# BikeLight_POC.net
KiCad netlist of a schematic drawn in EAGLE
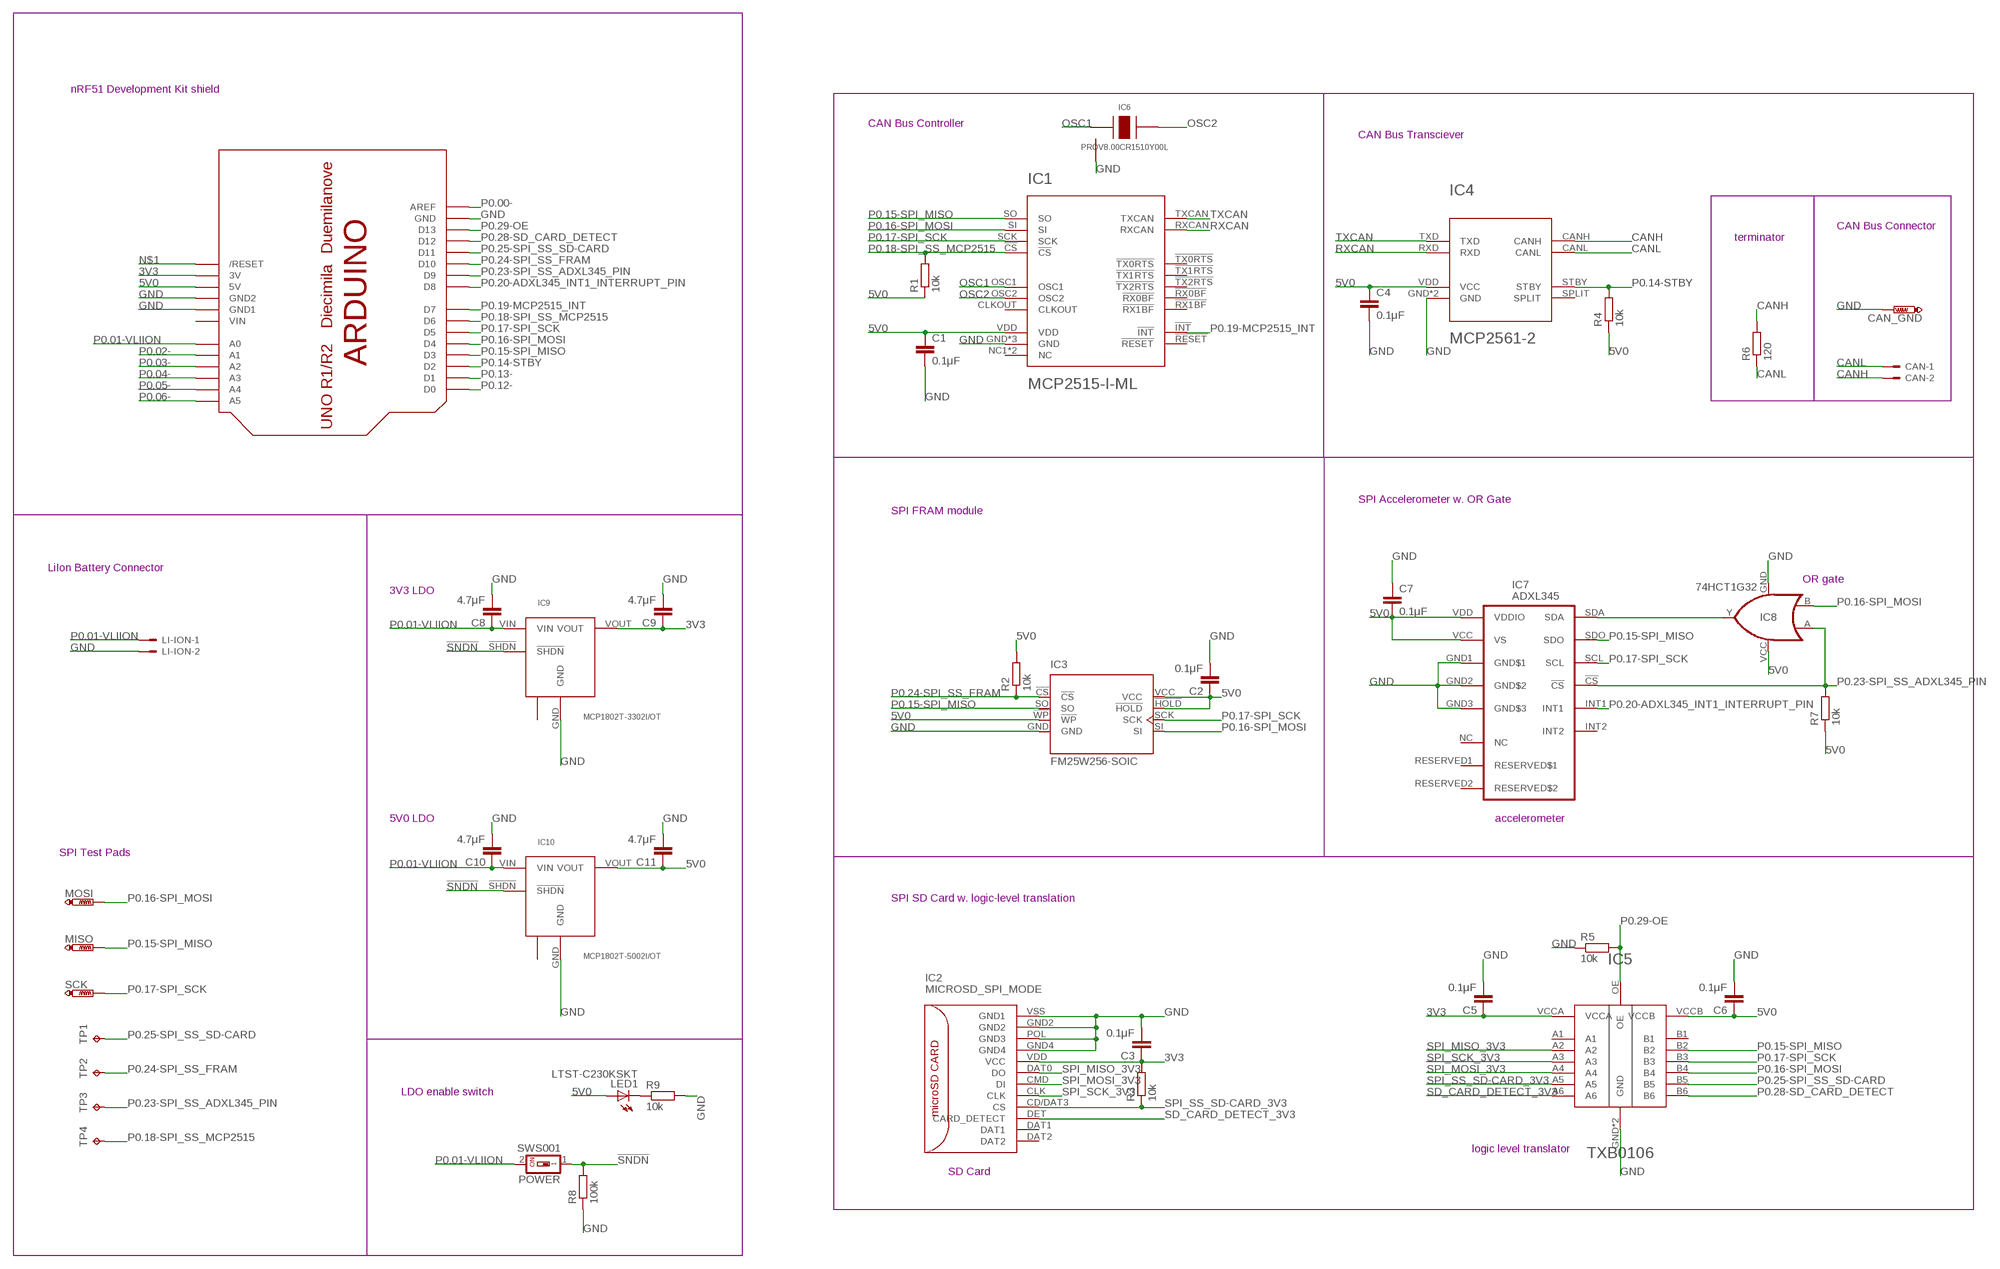
[diagram p0: schematic, sheet 1]

(export (version "E")
  (design (tool "Eeschema 10.0.6"))
  (components
    (comp (ref "BRD1")
      (value "BikeLight POC")
      (footprint "eagle-import:ARDUINO")
      (libsource (lib "eagle-import") (part "ARDUINOUNO"))
    )
    (comp (ref "C1")
      (value "0.1μF")
      (footprint "eagle-import:C0805")
      (libsource (lib "eagle-import") (part "C-EUC0805"))
    )
    (comp (ref "C2")
      (value "0.1μF")
      (footprint "eagle-import:C0805")
      (libsource (lib "eagle-import") (part "C-EUC0805"))
    )
    (comp (ref "C3")
      (value "0.1μF")
      (footprint "eagle-import:C0805")
      (libsource (lib "eagle-import") (part "C-EUC0805"))
    )
    (comp (ref "C4")
      (value "0.1μF")
      (footprint "eagle-import:C0805")
      (libsource (lib "eagle-import") (part "C-EUC0805"))
    )
    (comp (ref "C5")
      (value "0.1μF")
      (footprint "eagle-import:C0805")
      (libsource (lib "eagle-import") (part "C-EUC0805"))
    )
    (comp (ref "C6")
      (value "0.1μF")
      (footprint "eagle-import:C0805")
      (libsource (lib "eagle-import") (part "C-EUC0805"))
    )
    (comp (ref "C7")
      (value "0.1μF")
      (footprint "eagle-import:C0805")
      (libsource (lib "eagle-import") (part "C-EUC0805"))
    )
    (comp (ref "C8")
      (value "4.7μF")
      (footprint "eagle-import:C0805")
      (libsource (lib "eagle-import") (part "C-EUC0805"))
    )
    (comp (ref "C9")
      (value "4.7μF")
      (footprint "eagle-import:C0805")
      (libsource (lib "eagle-import") (part "C-EUC0805"))
    )
    (comp (ref "C10")
      (value "4.7μF")
      (footprint "eagle-import:C0805")
      (libsource (lib "eagle-import") (part "C-EUC0805"))
    )
    (comp (ref "C11")
      (value "4.7μF")
      (footprint "eagle-import:C0805")
      (libsource (lib "eagle-import") (part "C-EUC0805"))
    )
    (comp (ref "CAN")
      (value "22-23-2021")
      (footprint "eagle-import:22-23-2021")
      (fields (field (name "MF") "MOLEX"))
      (libsource (lib "eagle-import") (part "22-23-2021"))
    )
    (comp (ref "CAN_GND")
      (value "PTR1PAD1-13Y")
      (footprint "eagle-import:P1-13Y")
      (libsource (lib "eagle-import") (part "PTR1PAD1-13Y"))
    )
    (comp (ref "IC1")
      (value "MCP2515-I-ML")
      (footprint "eagle-import:QFN20")
      (libsource (lib "eagle-import") (part "MCP2515-I-ML"))
    )
    (comp (ref "IC2")
      (value "MICROSD_SPI_MODE")
      (footprint "eagle-import:MICRO_SD_CONNECTOR")
      (libsource (lib "eagle-import") (part "MICROSD_SPI_MODE"))
    )
    (comp (ref "IC3")
      (value "FM25W256-SOIC")
      (footprint "eagle-import:SOIC08")
      (libsource (lib "eagle-import") (part "FM25W256-SOIC"))
    )
    (comp (ref "IC4")
      (value "MCP2561-2")
      (footprint "eagle-import:DFN10")
      (libsource (lib "eagle-import") (part "MCP2561-2"))
    )
    (comp (ref "IC5")
      (value "TXB0106")
      (footprint "eagle-import:VQFN16")
      (libsource (lib "eagle-import") (part "TXB0106"))
    )
    (comp (ref "IC6")
      (value "PRQV8.00CR1510Y00L")
      (footprint "eagle-import:SMT")
      (libsource (lib "eagle-import") (part "PRQV"))
    )
    (comp (ref "IC7")
      (value "ADXL345")
      (footprint "eagle-import:LGA14")
      (libsource (lib "eagle-import") (part "ADXL345"))
    )
    (comp (ref "IC8")
      (value "74HCT1G32")
      (footprint "eagle-import:SOT353_5")
      (libsource (lib "eagle-import") (part "74HCT1G32GW-DC"))
    )
    (comp (ref "IC9")
      (value "MCP1802T-3302I/OT")
      (footprint "eagle-import:SOT23-5")
      (libsource (lib "eagle-import") (part "MCP1802"))
    )
    (comp (ref "IC10")
      (value "MCP1802T-5002I/OT")
      (footprint "eagle-import:SOT23-5")
      (libsource (lib "eagle-import") (part "MCP1802"))
    )
    (comp (ref "LED1")
      (value "LTST-C230KSKT")
      (footprint "eagle-import:CHIPLED_1206")
      (libsource (lib "eagle-import") (part "LEDCHIPLED_1206"))
    )
    (comp (ref "LI-ION")
      (value "22-23-2021")
      (footprint "eagle-import:22-23-2021")
      (fields (field (name "MF") "MOLEX"))
      (libsource (lib "eagle-import") (part "22-23-2021"))
    )
    (comp (ref "MISO")
      (value "PTR1PAD1-13Y")
      (footprint "eagle-import:P1-13Y")
      (libsource (lib "eagle-import") (part "PTR1PAD1-13Y"))
    )
    (comp (ref "MOSI")
      (value "PTR1PAD1-13Y")
      (footprint "eagle-import:P1-13Y")
      (libsource (lib "eagle-import") (part "PTR1PAD1-13Y"))
    )
    (comp (ref "POWER")
      (value "SWS001")
      (footprint "eagle-import:SMS-001")
      (libsource (lib "eagle-import") (part "SWS001"))
    )
    (comp (ref "R1")
      (value "10k")
      (footprint "eagle-import:R0805")
      (libsource (lib "eagle-import") (part "R-EU_R0805"))
    )
    (comp (ref "R2")
      (value "10k")
      (footprint "eagle-import:R0805")
      (libsource (lib "eagle-import") (part "R-EU_R0805"))
    )
    (comp (ref "R3")
      (value "10k")
      (footprint "eagle-import:R0805")
      (libsource (lib "eagle-import") (part "R-EU_R0805"))
    )
    (comp (ref "R4")
      (value "10k")
      (footprint "eagle-import:R0805")
      (libsource (lib "eagle-import") (part "R-EU_R0805"))
    )
    (comp (ref "R5")
      (value "10k")
      (footprint "eagle-import:R0805")
      (libsource (lib "eagle-import") (part "R-EU_R0805"))
    )
    (comp (ref "R6")
      (value "120")
      (footprint "eagle-import:R0805")
      (libsource (lib "eagle-import") (part "R-EU_R0805"))
    )
    (comp (ref "R7")
      (value "10k")
      (footprint "eagle-import:R0805")
      (libsource (lib "eagle-import") (part "R-EU_R0805"))
    )
    (comp (ref "R8")
      (value "100k")
      (footprint "eagle-import:R0805")
      (libsource (lib "eagle-import") (part "R-EU_R0805"))
    )
    (comp (ref "R9")
      (value "10k")
      (footprint "eagle-import:R0805")
      (libsource (lib "eagle-import") (part "R-EU_R0805"))
    )
    (comp (ref "SCK")
      (value "PTR1PAD1-13Y")
      (footprint "eagle-import:P1-13Y")
      (libsource (lib "eagle-import") (part "PTR1PAD1-13Y"))
    )
    (comp (ref "TP1")
      (value "TPPAD1-13")
      (footprint "eagle-import:P1-13")
      (libsource (lib "eagle-import") (part "TPPAD1-13"))
    )
    (comp (ref "TP2")
      (value "TPPAD1-13")
      (footprint "eagle-import:P1-13")
      (libsource (lib "eagle-import") (part "TPPAD1-13"))
    )
    (comp (ref "TP3")
      (value "TPPAD1-13")
      (footprint "eagle-import:P1-13")
      (libsource (lib "eagle-import") (part "TPPAD1-13"))
    )
    (comp (ref "TP4")
      (value "TPPAD1-13")
      (footprint "eagle-import:P1-13")
      (libsource (lib "eagle-import") (part "TPPAD1-13"))
    )
  )
  (nets
    (net (code "1") (name "/3V3") (class "Default")
      (node (ref "BRD1") (pin "3V") (pinfunction "3V_3V") (pintype "power_in"))
      (node (ref "C3") (pin "1") (pinfunction "1_1") (pintype "passive"))
      (node (ref "C5") (pin "1") (pinfunction "1_1") (pintype "passive"))
      (node (ref "C9") (pin "1") (pinfunction "1_1") (pintype "passive"))
      (node (ref "IC2") (pin "VDD") (pinfunction "VCC_VDD") (pintype "bidirectional"))
      (node (ref "IC5") (pin "VCCA") (pinfunction "VCCA_VCCA") (pintype "bidirectional"))
      (node (ref "IC9") (pin "VOUT") (pinfunction "VOUT_VOUT") (pintype "bidirectional"))
      (node (ref "R3") (pin "2") (pinfunction "2_2") (pintype "passive"))
    )
    (net (code "2") (name "/5V0") (class "Default")
      (node (ref "BRD1") (pin "5V") (pinfunction "5V_5V") (pintype "power_in"))
      (node (ref "C1") (pin "1") (pinfunction "1_1") (pintype "passive"))
      (node (ref "C11") (pin "1") (pinfunction "1_1") (pintype "passive"))
      (node (ref "C2") (pin "1") (pinfunction "1_1") (pintype "passive"))
      (node (ref "C4") (pin "1") (pinfunction "1_1") (pintype "passive"))
      (node (ref "C6") (pin "1") (pinfunction "1_1") (pintype "passive"))
      (node (ref "C7") (pin "2") (pinfunction "2_2") (pintype "passive"))
      (node (ref "IC1") (pin "VDD") (pinfunction "VDD_VDD") (pintype "power_in"))
      (node (ref "IC10") (pin "VOUT") (pinfunction "VOUT_VOUT") (pintype "bidirectional"))
      (node (ref "IC3") (pin "!HOLD!") (pinfunction "~{HOLD}_!HOLD!") (pintype "bidirectional"))
      (node (ref "IC3") (pin "!WP!") (pinfunction "~{WP}_!WP!") (pintype "bidirectional"))
      (node (ref "IC3") (pin "VCC") (pinfunction "VCC_VCC") (pintype "power_in"))
      (node (ref "IC4") (pin "VDD") (pinfunction "VCC_VDD") (pintype "power_in"))
      (node (ref "IC5") (pin "VCCB") (pinfunction "VCCB_VCCB") (pintype "bidirectional"))
      (node (ref "IC7") (pin "VCC") (pinfunction "VS_VCC") (pintype "power_in"))
      (node (ref "IC7") (pin "VDD") (pinfunction "VDDIO_VDD") (pintype "power_in"))
      (node (ref "IC8") (pin "VCC") (pinfunction "VCC_VCC") (pintype "power_in"))
      (node (ref "LED1") (pin "A") (pinfunction "A_A") (pintype "passive"))
      (node (ref "R1") (pin "1") (pinfunction "1_1") (pintype "passive"))
      (node (ref "R2") (pin "2") (pinfunction "2_2") (pintype "passive"))
      (node (ref "R4") (pin "1") (pinfunction "1_1") (pintype "passive"))
      (node (ref "R7") (pin "1") (pinfunction "1_1") (pintype "passive"))
    )
    (net (code "3") (name "/CANH") (class "Default")
      (node (ref "CAN") (pin "2") (pinfunction "S_2") (pintype "passive"))
      (node (ref "IC4") (pin "CANH") (pinfunction "CANH_CANH") (pintype "bidirectional"))
      (node (ref "R6") (pin "2") (pinfunction "2_2") (pintype "passive"))
    )
    (net (code "4") (name "/CANL") (class "Default")
      (node (ref "CAN") (pin "1") (pinfunction "S_1") (pintype "passive"))
      (node (ref "IC4") (pin "CANL") (pinfunction "CANL_CANL") (pintype "bidirectional"))
      (node (ref "R6") (pin "1") (pinfunction "1_1") (pintype "passive"))
    )
    (net (code "5") (name "/GND") (class "Default")
      (node (ref "BRD1") (pin "GND") (pinfunction "GND_GND") (pintype "power_in"))
      (node (ref "BRD1") (pin "GND1") (pinfunction "GND1_GND1") (pintype "power_in"))
      (node (ref "BRD1") (pin "GND2") (pinfunction "GND2_GND2") (pintype "power_in"))
      (node (ref "C1") (pin "2") (pinfunction "2_2") (pintype "passive"))
      (node (ref "C10") (pin "2") (pinfunction "2_2") (pintype "passive"))
      (node (ref "C11") (pin "2") (pinfunction "2_2") (pintype "passive"))
      (node (ref "C2") (pin "2") (pinfunction "2_2") (pintype "passive"))
      (node (ref "C3") (pin "2") (pinfunction "2_2") (pintype "passive"))
      (node (ref "C4") (pin "2") (pinfunction "2_2") (pintype "passive"))
      (node (ref "C5") (pin "2") (pinfunction "2_2") (pintype "passive"))
      (node (ref "C6") (pin "2") (pinfunction "2_2") (pintype "passive"))
      (node (ref "C7") (pin "1") (pinfunction "1_1") (pintype "passive"))
      (node (ref "C8") (pin "2") (pinfunction "2_2") (pintype "passive"))
      (node (ref "C9") (pin "2") (pinfunction "2_2") (pintype "passive"))
      (node (ref "CAN_GND") (pin "TP") (pinfunction "TP_TP") (pintype "input"))
      (node (ref "IC1") (pin "GND") (pinfunction "GND_GND") (pintype "power_in"))
      (node (ref "IC1") (pin "GND1") (pinfunction "GND_GND1") (pintype "power_in"))
      (node (ref "IC1") (pin "GND6") (pinfunction "GND_GND6") (pintype "power_in"))
      (node (ref "IC10") (pin "GND") (pinfunction "GND_GND") (pintype "bidirectional"))
      (node (ref "IC2") (pin "GND2") (pinfunction "GND2_GND2") (pintype "bidirectional"))
      (node (ref "IC2") (pin "GND4") (pinfunction "GND4_GND4") (pintype "bidirectional"))
      (node (ref "IC2") (pin "POL") (pinfunction "GND3_POL") (pintype "bidirectional"))
      (node (ref "IC2") (pin "VSS") (pinfunction "GND1_VSS") (pintype "bidirectional"))
      (node (ref "IC3") (pin "GND") (pinfunction "GND_GND") (pintype "power_in"))
      (node (ref "IC4") (pin "GND") (pinfunction "GND_GND") (pintype "power_in"))
      (node (ref "IC4") (pin "VSS") (pinfunction "GND_VSS") (pintype "power_in"))
      (node (ref "IC5") (pin "GND") (pinfunction "GND_GND") (pintype "bidirectional"))
      (node (ref "IC5") (pin "GND1") (pinfunction "GND_GND1") (pintype "bidirectional"))
      (node (ref "IC6") (pin "GND") (pinfunction "GND_GND") (pintype "bidirectional"))
      (node (ref "IC7") (pin "GND1") (pinfunction "GND$1_GND1") (pintype "power_in"))
      (node (ref "IC7") (pin "GND2") (pinfunction "GND$2_GND2") (pintype "power_in"))
      (node (ref "IC7") (pin "GND3") (pinfunction "GND$3_GND3") (pintype "power_in"))
      (node (ref "IC8") (pin "GND") (pinfunction "GND_GND") (pintype "power_in"))
      (node (ref "IC9") (pin "GND") (pinfunction "GND_GND") (pintype "bidirectional"))
      (node (ref "LI-ION") (pin "2") (pinfunction "S_2") (pintype "passive"))
      (node (ref "R5") (pin "1") (pinfunction "1_1") (pintype "passive"))
      (node (ref "R8") (pin "1") (pinfunction "1_1") (pintype "passive"))
      (node (ref "R9") (pin "2") (pinfunction "2_2") (pintype "passive"))
    )
    (net (code "6") (name "/N$1") (class "Default")
      (node (ref "BRD1") (pin "RESET") (pinfunction "/RESET_RESET") (pintype "bidirectional"))
    )
    (net (code "7") (name "/OSC1") (class "Default")
      (node (ref "IC1") (pin "OSC1") (pinfunction "OSC1_OSC1") (pintype "bidirectional"))
      (node (ref "IC6") (pin "XTAL1") (pinfunction "XTAL1_XTAL1") (pintype "bidirectional"))
    )
    (net (code "8") (name "/OSC2") (class "Default")
      (node (ref "IC1") (pin "OSC2") (pinfunction "OSC2_OSC2") (pintype "bidirectional"))
      (node (ref "IC6") (pin "XTAL2") (pinfunction "XTAL2_XTAL2") (pintype "bidirectional"))
    )
    (net (code "9") (name "/P0.00-") (class "Default")
      (node (ref "BRD1") (pin "AREF") (pinfunction "AREF_AREF") (pintype "bidirectional"))
    )
    (net (code "10") (name "/P0.01-VLIION") (class "Default")
      (node (ref "BRD1") (pin "A0") (pinfunction "A0_A0") (pintype "bidirectional"))
      (node (ref "C10") (pin "1") (pinfunction "1_1") (pintype "passive"))
      (node (ref "C8") (pin "1") (pinfunction "1_1") (pintype "passive"))
      (node (ref "IC10") (pin "VIN") (pinfunction "VIN_VIN") (pintype "bidirectional"))
      (node (ref "IC9") (pin "VIN") (pinfunction "VIN_VIN") (pintype "bidirectional"))
      (node (ref "LI-ION") (pin "1") (pinfunction "S_1") (pintype "passive"))
      (node (ref "POWER") (pin "2") (pinfunction "2_2") (pintype "passive"))
    )
    (net (code "11") (name "/P0.02-") (class "Default")
      (node (ref "BRD1") (pin "A1") (pinfunction "A1_A1") (pintype "bidirectional"))
    )
    (net (code "12") (name "/P0.03-") (class "Default")
      (node (ref "BRD1") (pin "A2") (pinfunction "A2_A2") (pintype "bidirectional"))
    )
    (net (code "13") (name "/P0.04-") (class "Default")
      (node (ref "BRD1") (pin "A3") (pinfunction "A3_A3") (pintype "bidirectional"))
    )
    (net (code "14") (name "/P0.05-") (class "Default")
      (node (ref "BRD1") (pin "A4") (pinfunction "A4_A4") (pintype "bidirectional"))
    )
    (net (code "15") (name "/P0.06-") (class "Default")
      (node (ref "BRD1") (pin "A5") (pinfunction "A5_A5") (pintype "bidirectional"))
    )
    (net (code "16") (name "/P0.12-") (class "Default")
      (node (ref "BRD1") (pin "D0") (pinfunction "D0_D0") (pintype "bidirectional"))
    )
    (net (code "17") (name "/P0.13-") (class "Default")
      (node (ref "BRD1") (pin "D1") (pinfunction "D1_D1") (pintype "bidirectional"))
    )
    (net (code "18") (name "/P0.14-STBY") (class "Default")
      (node (ref "BRD1") (pin "D2") (pinfunction "D2_D2") (pintype "bidirectional"))
      (node (ref "IC4") (pin "STBY") (pinfunction "STBY_STBY") (pintype "bidirectional"))
      (node (ref "R4") (pin "2") (pinfunction "2_2") (pintype "passive"))
    )
    (net (code "19") (name "/P0.15-SPI_MISO") (class "Default")
      (node (ref "BRD1") (pin "D3") (pinfunction "D3_D3") (pintype "bidirectional"))
      (node (ref "IC1") (pin "SO") (pinfunction "SO_SO") (pintype "output"))
      (node (ref "IC3") (pin "SO") (pinfunction "SO_SO") (pintype "bidirectional"))
      (node (ref "IC5") (pin "B2") (pinfunction "B2_B2") (pintype "bidirectional"))
      (node (ref "IC7") (pin "SDO") (pinfunction "SDO_SDO") (pintype "output"))
      (node (ref "MISO") (pin "TP") (pinfunction "TP_TP") (pintype "input"))
    )
    (net (code "20") (name "/P0.16-SPI_MOSI") (class "Default")
      (node (ref "BRD1") (pin "D4") (pinfunction "D4_D4") (pintype "bidirectional"))
      (node (ref "IC1") (pin "SI") (pinfunction "SI_SI") (pintype "input"))
      (node (ref "IC3") (pin "SI") (pinfunction "SI_SI") (pintype "bidirectional"))
      (node (ref "IC5") (pin "B4") (pinfunction "B4_B4") (pintype "bidirectional"))
      (node (ref "IC8") (pin "B") (pinfunction "B_B") (pintype "input"))
      (node (ref "MOSI") (pin "TP") (pinfunction "TP_TP") (pintype "input"))
    )
    (net (code "21") (name "/P0.17-SPI_SCK") (class "Default")
      (node (ref "BRD1") (pin "D5") (pinfunction "D5_D5") (pintype "bidirectional"))
      (node (ref "IC1") (pin "SCK") (pinfunction "SCK_SCK") (pintype "bidirectional"))
      (node (ref "IC3") (pin "SCK") (pinfunction "SCK_SCK") (pintype "bidirectional"))
      (node (ref "IC5") (pin "B3") (pinfunction "B3_B3") (pintype "bidirectional"))
      (node (ref "IC7") (pin "SCL") (pinfunction "SCL_SCL") (pintype "input"))
      (node (ref "SCK") (pin "TP") (pinfunction "TP_TP") (pintype "input"))
    )
    (net (code "22") (name "/P0.18-SPI_SS_MCP2515") (class "Default")
      (node (ref "BRD1") (pin "D6") (pinfunction "D6_D6") (pintype "bidirectional"))
      (node (ref "IC1") (pin "!CS!") (pinfunction "~{CS}_!CS!") (pintype "bidirectional"))
      (node (ref "R1") (pin "2") (pinfunction "2_2") (pintype "passive"))
      (node (ref "TP4") (pin "TP") (pinfunction "TP_TP") (pintype "input"))
    )
    (net (code "23") (name "/P0.19-MCP2515_INT") (class "Default")
      (node (ref "BRD1") (pin "D7") (pinfunction "D7_D7") (pintype "bidirectional"))
      (node (ref "IC1") (pin "!INT!") (pinfunction "~{INT}_!INT!") (pintype "bidirectional"))
    )
    (net (code "24") (name "/P0.20-ADXL345_INT1_INTERRUPT_PIN") (class "Default")
      (node (ref "BRD1") (pin "D8") (pinfunction "D8_D8") (pintype "bidirectional"))
      (node (ref "IC7") (pin "INT1") (pinfunction "INT1_INT1") (pintype "output"))
    )
    (net (code "25") (name "/P0.23-SPI_SS_ADXL345_PIN") (class "Default")
      (node (ref "BRD1") (pin "D9") (pinfunction "D9_D9") (pintype "bidirectional"))
      (node (ref "IC7") (pin "!CS!") (pinfunction "~{CS}_!CS!") (pintype "input"))
      (node (ref "IC8") (pin "A") (pinfunction "A_A") (pintype "input"))
      (node (ref "R7") (pin "2") (pinfunction "2_2") (pintype "passive"))
      (node (ref "TP3") (pin "TP") (pinfunction "TP_TP") (pintype "input"))
    )
    (net (code "26") (name "/P0.24-SPI_SS_FRAM") (class "Default")
      (node (ref "BRD1") (pin "D10") (pinfunction "D10_D10") (pintype "bidirectional"))
      (node (ref "IC3") (pin "!CS!") (pinfunction "~{CS}_!CS!") (pintype "bidirectional"))
      (node (ref "R2") (pin "1") (pinfunction "1_1") (pintype "passive"))
      (node (ref "TP2") (pin "TP") (pinfunction "TP_TP") (pintype "input"))
    )
    (net (code "27") (name "/P0.25-SPI_SS_SD-CARD") (class "Default")
      (node (ref "BRD1") (pin "D11") (pinfunction "D11_D11") (pintype "bidirectional"))
      (node (ref "IC5") (pin "B5") (pinfunction "B5_B5") (pintype "bidirectional"))
      (node (ref "TP1") (pin "TP") (pinfunction "TP_TP") (pintype "input"))
    )
    (net (code "28") (name "/P0.28-SD_CARD_DETECT") (class "Default")
      (node (ref "BRD1") (pin "D12") (pinfunction "D12_D12") (pintype "bidirectional"))
      (node (ref "IC5") (pin "B6") (pinfunction "B6_B6") (pintype "bidirectional"))
    )
    (net (code "29") (name "/P0.29-OE") (class "Default")
      (node (ref "BRD1") (pin "D13") (pinfunction "D13_D13") (pintype "bidirectional"))
      (node (ref "IC5") (pin "OE") (pinfunction "OE_OE") (pintype "bidirectional"))
      (node (ref "R5") (pin "2") (pinfunction "2_2") (pintype "passive"))
    )
    (net (code "30") (name "/RXCAN") (class "Default")
      (node (ref "IC1") (pin "RXCAN") (pinfunction "RXCAN_RXCAN") (pintype "input"))
      (node (ref "IC4") (pin "RXD") (pinfunction "RXD_RXD") (pintype "output"))
    )
    (net (code "31") (name "/SD_CARD_DETECT_3V3") (class "Default")
      (node (ref "IC2") (pin "DET") (pinfunction "CARD_DETECT_DET") (pintype "bidirectional"))
      (node (ref "IC5") (pin "A6") (pinfunction "A6_A6") (pintype "bidirectional"))
    )
    (net (code "32") (name "/SPI_MISO_3V3") (class "Default")
      (node (ref "IC2") (pin "DAT0") (pinfunction "DO_DAT0") (pintype "bidirectional"))
      (node (ref "IC5") (pin "A2") (pinfunction "A2_A2") (pintype "bidirectional"))
    )
    (net (code "33") (name "/SPI_MOSI_3V3") (class "Default")
      (node (ref "IC2") (pin "CMD") (pinfunction "DI_CMD") (pintype "bidirectional"))
      (node (ref "IC5") (pin "A4") (pinfunction "A4_A4") (pintype "bidirectional"))
    )
    (net (code "34") (name "/SPI_SCK_3V3") (class "Default")
      (node (ref "IC2") (pin "CLK") (pinfunction "CLK_CLK") (pintype "bidirectional"))
      (node (ref "IC5") (pin "A3") (pinfunction "A3_A3") (pintype "bidirectional"))
    )
    (net (code "35") (name "/SPI_SS_SD-CARD_3V3") (class "Default")
      (node (ref "IC2") (pin "CD/DAT3") (pinfunction "CS_CD/DAT3") (pintype "bidirectional"))
      (node (ref "IC5") (pin "A5") (pinfunction "A5_A5") (pintype "bidirectional"))
      (node (ref "R3") (pin "1") (pinfunction "1_1") (pintype "passive"))
    )
    (net (code "36") (name "/TXCAN") (class "Default")
      (node (ref "IC1") (pin "TXCAN") (pinfunction "TXCAN_TXCAN") (pintype "output"))
      (node (ref "IC4") (pin "TXD") (pinfunction "TXD_TXD") (pintype "input"))
    )
    (net (code "37") (name "/VIN") (class "Default")
      (node (ref "BRD1") (pin "VIN") (pinfunction "VIN_VIN") (pintype "power_in"))
    )
    (net (code "38") (name "/~{SNDN}") (class "Default")
      (node (ref "IC10") (pin "!SHDN!") (pinfunction "~{SHDN}_!SHDN!") (pintype "bidirectional"))
      (node (ref "IC9") (pin "!SHDN!") (pinfunction "~{SHDN}_!SHDN!") (pintype "bidirectional"))
      (node (ref "POWER") (pin "1") (pinfunction "1_1") (pintype "passive"))
      (node (ref "R8") (pin "2") (pinfunction "2_2") (pintype "passive"))
    )
    (net (code "39") (name "Net-(IC7-PadSDA)") (class "Default")
      (node (ref "IC7") (pin "SDA") (pinfunction "SDA_SDA") (pintype "input"))
      (node (ref "IC8") (pin "Y") (pinfunction "Y_Y") (pintype "output"))
    )
    (net (code "40") (name "Net-(LED1-PadC)") (class "Default")
      (node (ref "LED1") (pin "C") (pinfunction "C_C") (pintype "passive"))
      (node (ref "R9") (pin "1") (pinfunction "1_1") (pintype "passive"))
    )
    (net (code "41") (name "unconnected-(IC1-NC-PadNC1)") (class "Default")
      (node (ref "IC1") (pin "NC1") (pinfunction "NC_NC1") (pintype "no_connect"))
    )
    (net (code "42") (name "unconnected-(IC1-NC-PadNC2)") (class "Default")
      (node (ref "IC1") (pin "NC2") (pinfunction "NC_NC2") (pintype "no_connect"))
    )
    (net (code "43") (name "unconnected-(IC1-PadCLKOUT)") (class "Default")
      (node (ref "IC1") (pin "CLKOUT") (pinfunction "CLKOUT_CLKOUT") (pintype "bidirectional"))
    )
    (net (code "44") (name "unconnected-(IC1-~{RESET}-Pad!RESET!)") (class "Default")
      (node (ref "IC1") (pin "!RESET!") (pinfunction "~{RESET}_!RESET!") (pintype "bidirectional"))
    )
    (net (code "45") (name "unconnected-(IC1-~{RX0BF}-Pad!RX0BF!)") (class "Default")
      (node (ref "IC1") (pin "!RX0BF!") (pinfunction "~{RX0BF}_!RX0BF!") (pintype "bidirectional"))
    )
    (net (code "46") (name "unconnected-(IC1-~{RX1BF}-Pad!RX1BF!)") (class "Default")
      (node (ref "IC1") (pin "!RX1BF!") (pinfunction "~{RX1BF}_!RX1BF!") (pintype "bidirectional"))
    )
    (net (code "47") (name "unconnected-(IC1-~{TX0RTS}-Pad!TX0RTS!)") (class "Default")
      (node (ref "IC1") (pin "!TX0RTS!") (pinfunction "~{TX0RTS}_!TX0RTS!") (pintype "bidirectional"))
    )
    (net (code "48") (name "unconnected-(IC1-~{TX1RTS}-Pad!TX1RTS!)") (class "Default")
      (node (ref "IC1") (pin "!TX1RTS!") (pinfunction "~{TX1RTS}_!TX1RTS!") (pintype "bidirectional"))
    )
    (net (code "49") (name "unconnected-(IC1-~{TX2RTS}-Pad!TX2RTS!)") (class "Default")
      (node (ref "IC1") (pin "!TX2RTS!") (pinfunction "~{TX2RTS}_!TX2RTS!") (pintype "bidirectional"))
    )
    (net (code "50") (name "unconnected-(IC2-PadDAT1)") (class "Default")
      (node (ref "IC2") (pin "DAT1") (pinfunction "DAT1_DAT1") (pintype "bidirectional"))
    )
    (net (code "51") (name "unconnected-(IC2-PadDAT2)") (class "Default")
      (node (ref "IC2") (pin "DAT2") (pinfunction "DAT2_DAT2") (pintype "bidirectional"))
    )
    (net (code "52") (name "unconnected-(IC4-PadSPLIT)") (class "Default")
      (node (ref "IC4") (pin "SPLIT") (pinfunction "SPLIT_SPLIT") (pintype "bidirectional"))
    )
    (net (code "53") (name "unconnected-(IC5-PadA1)") (class "Default")
      (node (ref "IC5") (pin "A1") (pinfunction "A1_A1") (pintype "bidirectional"))
    )
    (net (code "54") (name "unconnected-(IC5-PadB1)") (class "Default")
      (node (ref "IC5") (pin "B1") (pinfunction "B1_B1") (pintype "bidirectional"))
    )
    (net (code "55") (name "unconnected-(IC7-PadINT2)") (class "Default")
      (node (ref "IC7") (pin "INT2") (pinfunction "INT2_INT2") (pintype "output"))
    )
    (net (code "56") (name "unconnected-(IC7-PadNC)") (class "Default")
      (node (ref "IC7") (pin "NC") (pinfunction "NC_NC") (pintype "bidirectional"))
    )
    (net (code "57") (name "unconnected-(IC7-RESERVED$1-PadRESERVED1)") (class "Default")
      (node (ref "IC7") (pin "RESERVED1") (pinfunction "RESERVED$1_RESERVED1") (pintype "bidirectional"))
    )
    (net (code "58") (name "unconnected-(IC7-RESERVED$2-PadRESERVED2)") (class "Default")
      (node (ref "IC7") (pin "RESERVED2") (pinfunction "RESERVED$2_RESERVED2") (pintype "bidirectional"))
    )
    (net (code "59") (name "unconnected-(IC9-PadNC)") (class "Default")
      (node (ref "IC9") (pin "NC") (pinfunction "NC_NC") (pintype "no_connect"))
    )
    (net (code "60") (name "unconnected-(IC10-PadNC)") (class "Default")
      (node (ref "IC10") (pin "NC") (pinfunction "NC_NC") (pintype "no_connect"))
    )
  )
)
